# RGMII_Ethernet.net
KiCad netlist of a schematic drawn in Altium Designer
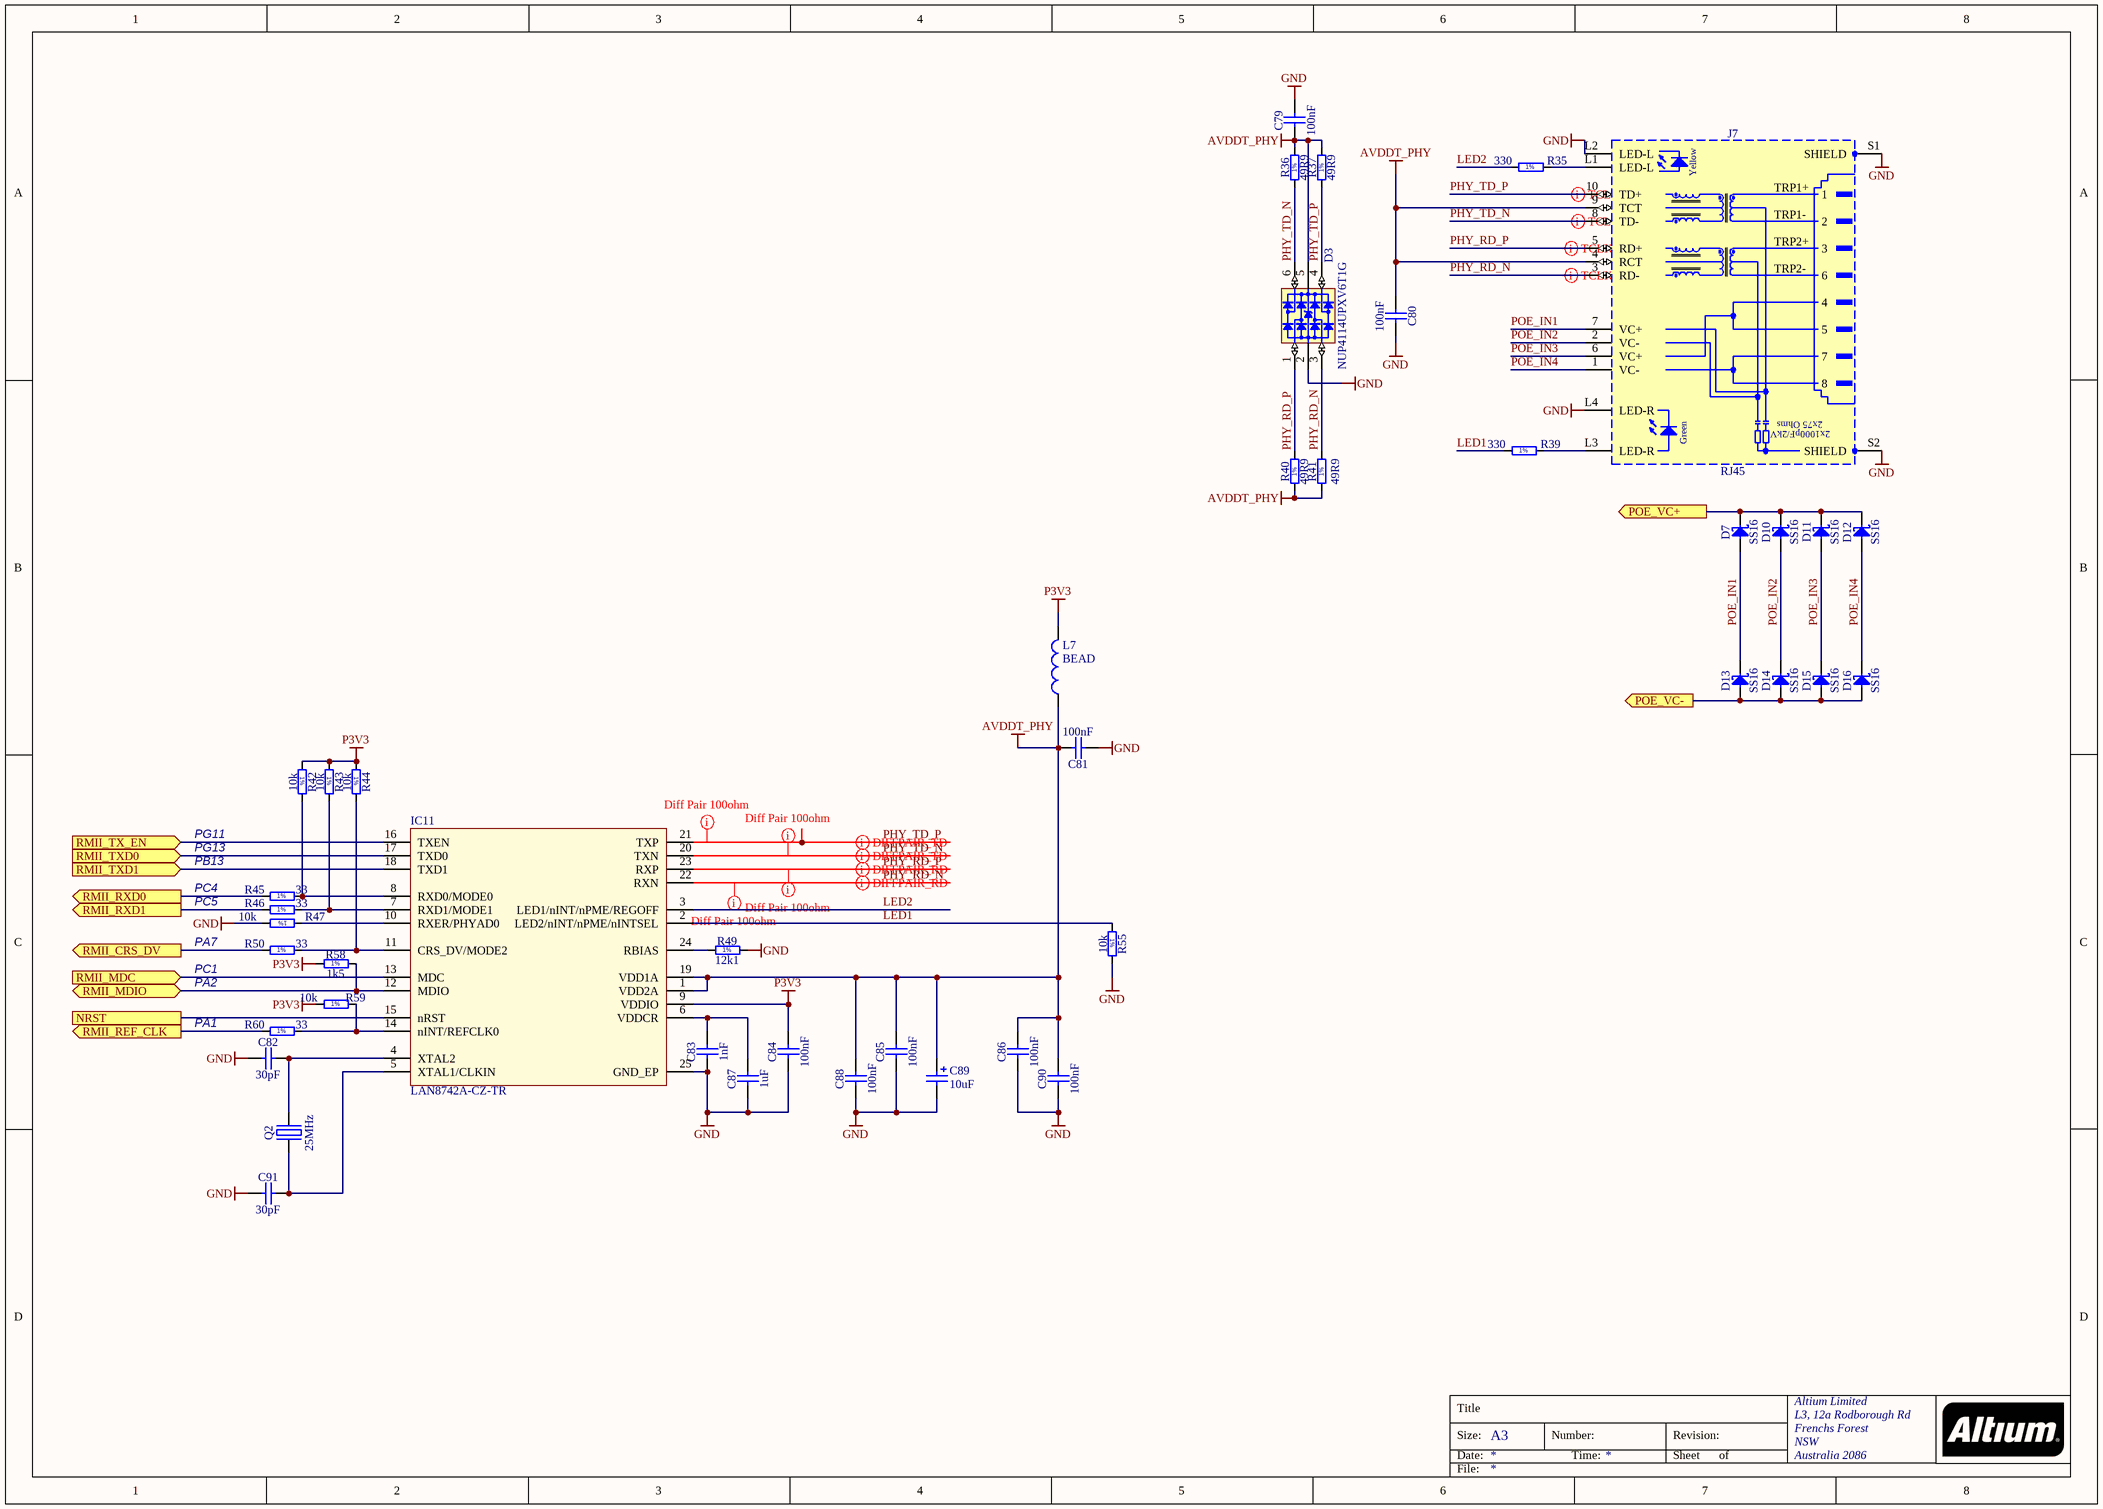
[diagram p0: RGMII_Ethernet.SchDoc]

(export (version "E")
  (design (tool "Eeschema 10.0.6"))
  (components
    (comp (ref "C79")
      (value "100nF")
      (footprint "CAPC1005X55N")
      (description "Non-polarised capacitor")
      (fields
        (field (name "PART NUMBER") "CC0402_100NF_16V_10%_X5R")
        (field (name "VOLTAGE") "16V")
        (field (name "AUTHOR") "CERN DEM JLC")
      )
      (libsource (lib "Capacitors") (part "Capacitor - non polarized"))
    )
    (comp (ref "C80")
      (value "100nF")
      (footprint "CAPC1005X55N")
      (description "Non-polarised capacitor")
      (fields
        (field (name "PART NUMBER") "CC0402_100NF_16V_10%_X5R")
        (field (name "VOLTAGE") "16V")
        (field (name "AUTHOR") "CERN DEM JLC")
      )
      (libsource (lib "Capacitors") (part "Capacitor - non polarized"))
    )
    (comp (ref "C81")
      (value "100nF")
      (footprint "CAPC1005X55N")
      (description "Non-polarised capacitor")
      (fields
        (field (name "PART NUMBER") "CC0402_100NF_16V_10%_X5R")
        (field (name "VOLTAGE") "16V")
        (field (name "AUTHOR") "CERN DEM JLC")
      )
      (libsource (lib "Capacitors") (part "Capacitor - non polarized"))
    )
    (comp (ref "C82")
      (value "30pF")
      (footprint "CAPC1005X55N")
      (description "Non-polarised capacitor")
      (fields
        (field (name "PART NUMBER") "CC0402_30PF_50V_1%_C0G_MURATA_GJM1555C1H300FB01")
        (field (name "VOLTAGE") "50V")
        (field (name "AUTHOR") "CERN DEM BC")
      )
      (libsource (lib "Capacitors") (part "Capacitor - non polarized"))
    )
    (comp (ref "C83")
      (value "1nF")
      (footprint "CAPC1005X55N")
      (description "Non-polarised capacitor")
      (fields
        (field (name "PART NUMBER") "CC0402_1NF_50V_10%_X7R")
        (field (name "VOLTAGE") "50V")
        (field (name "AUTHOR") "CERN DEM JLC")
      )
      (libsource (lib "Capacitors") (part "Capacitor - non polarized"))
    )
    (comp (ref "C84")
      (value "100nF")
      (footprint "CAPC1005X55N")
      (description "Non-polarised capacitor")
      (fields
        (field (name "PART NUMBER") "CC0402_100NF_16V_10%_X5R")
        (field (name "VOLTAGE") "16V")
        (field (name "AUTHOR") "CERN DEM JLC")
      )
      (libsource (lib "Capacitors") (part "Capacitor - non polarized"))
    )
    (comp (ref "C85")
      (value "100nF")
      (footprint "CAPC1005X55N")
      (description "Non-polarised capacitor")
      (fields
        (field (name "PART NUMBER") "CC0402_100NF_16V_10%_X5R")
        (field (name "VOLTAGE") "16V")
        (field (name "AUTHOR") "CERN DEM JLC")
      )
      (libsource (lib "Capacitors") (part "Capacitor - non polarized"))
    )
    (comp (ref "C86")
      (value "100nF")
      (footprint "CAPC1005X55N")
      (description "Non-polarised capacitor")
      (fields
        (field (name "PART NUMBER") "CC0402_100NF_16V_10%_X5R")
        (field (name "VOLTAGE") "16V")
        (field (name "AUTHOR") "CERN DEM JLC")
      )
      (libsource (lib "Capacitors") (part "Capacitor - non polarized"))
    )
    (comp (ref "C87")
      (value "1uF")
      (footprint "CAPC1608X87N")
      (description "Non-polarised capacitor")
      (fields
        (field (name "PART NUMBER") "CC0603_1UF_16V_10%_X7R")
        (field (name "VOLTAGE") "16V")
        (field (name "AUTHOR") "CERN DEM JLC")
      )
      (libsource (lib "Capacitors") (part "Capacitor - non polarized"))
    )
    (comp (ref "C88")
      (value "100nF")
      (footprint "CAPC1005X55N")
      (description "Non-polarised capacitor")
      (fields
        (field (name "PART NUMBER") "CC0402_100NF_16V_10%_X5R")
        (field (name "VOLTAGE") "16V")
        (field (name "AUTHOR") "CERN DEM JLC")
      )
      (libsource (lib "Capacitors") (part "Capacitor - non polarized"))
    )
    (comp (ref "C89")
      (value "10uF")
      (footprint "TAN-A")
      (description "Polarized Capacitor,10uF,10V,10%,typeA,VISHAY")
      (libsource (lib "MCD_TOOLS") (part "Cap_10uF_POL_10%_TANA"))
    )
    (comp (ref "C90")
      (value "100nF")
      (footprint "CAPC1005X55N")
      (description "Non-polarised capacitor")
      (fields
        (field (name "PART NUMBER") "CC0402_100NF_16V_10%_X5R")
        (field (name "VOLTAGE") "16V")
        (field (name "AUTHOR") "CERN DEM JLC")
      )
      (libsource (lib "Capacitors") (part "Capacitor - non polarized"))
    )
    (comp (ref "C91")
      (value "30pF")
      (footprint "CAPC1005X55N")
      (description "Non-polarised capacitor")
      (fields
        (field (name "PART NUMBER") "CC0402_30PF_50V_1%_C0G_MURATA_GJM1555C1H300FB01")
        (field (name "VOLTAGE") "50V")
        (field (name "AUTHOR") "CERN DEM BC")
      )
      (libsource (lib "Capacitors") (part "Capacitor - non polarized"))
    )
    (comp (ref "D3")
      (value "NUP4114UPXV6T1G")
      (footprint "SOTFL50P160X60-6N")
      (fields
        (field (name "VOLTAGE") "5.5V")
        (field (name "MANUFACTURER") "ON SEMICONDUCTOR")
        (field (name "AUTHOR") "CERN DEM JLC")
      )
      (libsource (lib "ICs And Semiconductors") (part "NUP4114"))
    )
    (comp (ref "D7")
      (value "SS16")
      (footprint "DIOM5127X229N")
      (description "Schottky Diode")
      (fields
        (field (name "VOLTAGE") "60V")
        (field (name "POWER") "1A")
        (field (name "AUTHOR") "CERN DEM JLC")
      )
      (libsource (lib "ICs And Semiconductors") (part "Diode Schottky"))
    )
    (comp (ref "D10")
      (value "SS16")
      (footprint "DIOM5127X229N")
      (description "Schottky Diode")
      (fields
        (field (name "VOLTAGE") "60V")
        (field (name "POWER") "1A")
        (field (name "AUTHOR") "CERN DEM JLC")
      )
      (libsource (lib "ICs And Semiconductors") (part "Diode Schottky"))
    )
    (comp (ref "D11")
      (value "SS16")
      (footprint "DIOM5127X229N")
      (description "Schottky Diode")
      (fields
        (field (name "VOLTAGE") "60V")
        (field (name "POWER") "1A")
        (field (name "AUTHOR") "CERN DEM JLC")
      )
      (libsource (lib "ICs And Semiconductors") (part "Diode Schottky"))
    )
    (comp (ref "D12")
      (value "SS16")
      (footprint "DIOM5127X229N")
      (description "Schottky Diode")
      (fields
        (field (name "VOLTAGE") "60V")
        (field (name "POWER") "1A")
        (field (name "AUTHOR") "CERN DEM JLC")
      )
      (libsource (lib "ICs And Semiconductors") (part "Diode Schottky"))
    )
    (comp (ref "D13")
      (value "SS16")
      (footprint "DIOM5127X229N")
      (description "Schottky Diode")
      (fields
        (field (name "VOLTAGE") "60V")
        (field (name "POWER") "1A")
        (field (name "AUTHOR") "CERN DEM JLC")
      )
      (libsource (lib "ICs And Semiconductors") (part "Diode Schottky"))
    )
    (comp (ref "D14")
      (value "SS16")
      (footprint "DIOM5127X229N")
      (description "Schottky Diode")
      (fields
        (field (name "VOLTAGE") "60V")
        (field (name "POWER") "1A")
        (field (name "AUTHOR") "CERN DEM JLC")
      )
      (libsource (lib "ICs And Semiconductors") (part "Diode Schottky"))
    )
    (comp (ref "D15")
      (value "SS16")
      (footprint "DIOM5127X229N")
      (description "Schottky Diode")
      (fields
        (field (name "VOLTAGE") "60V")
        (field (name "POWER") "1A")
        (field (name "AUTHOR") "CERN DEM JLC")
      )
      (libsource (lib "ICs And Semiconductors") (part "Diode Schottky"))
    )
    (comp (ref "D16")
      (value "SS16")
      (footprint "DIOM5127X229N")
      (description "Schottky Diode")
      (fields
        (field (name "VOLTAGE") "60V")
        (field (name "POWER") "1A")
        (field (name "AUTHOR") "CERN DEM JLC")
      )
      (libsource (lib "ICs And Semiconductors") (part "Diode Schottky"))
    )
    (comp (ref "IC11")
      (value "LAN8742A-CZ-TR")
      (footprint "QFN24_0R5_4X4")
      (libsource (lib "LIBRARY_SCH") (part "IFC_LAN8742A"))
    )
    (comp (ref "J7")
      (value "RJ45")
      (footprint "ABRACON_ARJM11C7-114-BA-EW2")
      (description "MagJack 10/100BaseT, PoE+, 1X1, OG/Y, -40 to 85*C, Tab Up, RoHS")
      (fields
        (field (name "PART NUMBER") "ARJM11C7-114-BA-EW2")
        (field (name "MANUFACTURER") "Abracon")
        (field (name "AUTHOR") "GK")
      )
      (libsource (lib "LIBRARY_SCH") (part "CON_ETH_POE_ARJM11C7"))
    )
    (comp (ref "L7")
      (value "BEAD")
      (footprint "0603L")
      (description "Inductor")
      (fields (field (name "PUBLISHER") "Altium Limited"))
      (libsource (lib "Miscellaneous Devices") (part "Inductor"))
    )
    (comp (ref "Q2")
      (value "25MHz")
      (footprint "XTAL_ABRACON_ABLS")
      (description "Quartz Crystal")
      (fields
        (field (name "PART NUMBER") "XTAL_25MHZ_ABRACON_ABLS-25.000MHZ-B2F-T")
        (field (name "MANUFACTURER") "ABRACON")
        (field (name "AUTHOR") "CERN DEM JLC")
      )
      (libsource (lib "ICs And Semiconductors") (part "Quartz Crystal"))
    )
    (comp (ref "R35")
      (value "330")
      (footprint "RESC1005X40N")
      (description "Resistor - 1%")
      (fields
        (field (name "PART NUMBER") "R0402_330R_1%_0.0625W_100PPM")
        (field (name "POWER") "0.0625W")
        (field (name "AUTHOR") "CERN DEM JLC")
      )
      (libsource (lib "Resistors") (part "Resistor - 1%"))
    )
    (comp (ref "R36")
      (value "49R9")
      (footprint "RESC1005X40N")
      (description "Resistor - 1%")
      (fields
        (field (name "PART NUMBER") "R0402_49R9_1%_0.0625W_100PPM")
        (field (name "POWER") "0.0625W")
        (field (name "AUTHOR") "CERN DEM JLC")
      )
      (libsource (lib "Resistors") (part "Resistor - 1%"))
    )
    (comp (ref "R37")
      (value "49R9")
      (footprint "RESC1005X40N")
      (description "Resistor - 1%")
      (fields
        (field (name "PART NUMBER") "R0402_49R9_1%_0.0625W_100PPM")
        (field (name "POWER") "0.0625W")
        (field (name "AUTHOR") "CERN DEM JLC")
      )
      (libsource (lib "Resistors") (part "Resistor - 1%"))
    )
    (comp (ref "R39")
      (value "330")
      (footprint "RESC1005X40N")
      (description "Resistor - 1%")
      (fields
        (field (name "PART NUMBER") "R0402_330R_1%_0.0625W_100PPM")
        (field (name "POWER") "0.0625W")
        (field (name "AUTHOR") "CERN DEM JLC")
      )
      (libsource (lib "Resistors") (part "Resistor - 1%"))
    )
    (comp (ref "R40")
      (value "49R9")
      (footprint "RESC1005X40N")
      (description "Resistor - 1%")
      (fields
        (field (name "PART NUMBER") "R0402_49R9_1%_0.0625W_100PPM")
        (field (name "POWER") "0.0625W")
        (field (name "AUTHOR") "CERN DEM JLC")
      )
      (libsource (lib "Resistors") (part "Resistor - 1%"))
    )
    (comp (ref "R41")
      (value "49R9")
      (footprint "RESC1005X40N")
      (description "Resistor - 1%")
      (fields
        (field (name "PART NUMBER") "R0402_49R9_1%_0.0625W_100PPM")
        (field (name "POWER") "0.0625W")
        (field (name "AUTHOR") "CERN DEM JLC")
      )
      (libsource (lib "Resistors") (part "Resistor - 1%"))
    )
    (comp (ref "R42")
      (value "10k")
      (footprint "RESC1005X40N")
      (description "Resistor - 1%")
      (fields
        (field (name "PART NUMBER") "R0402_10K_1%_0.0625W_100PPM")
        (field (name "POWER") "0.0625W")
        (field (name "AUTHOR") "CERN DEM JLC")
      )
      (libsource (lib "Resistors") (part "Resistor - 1%"))
    )
    (comp (ref "R43")
      (value "10k")
      (footprint "RESC1005X40N")
      (description "Resistor - 1%")
      (fields
        (field (name "PART NUMBER") "R0402_10K_1%_0.0625W_100PPM")
        (field (name "POWER") "0.0625W")
        (field (name "AUTHOR") "CERN DEM JLC")
      )
      (libsource (lib "Resistors") (part "Resistor - 1%"))
    )
    (comp (ref "R44")
      (value "10k")
      (footprint "RESC1005X40N")
      (description "Resistor - 1%")
      (fields
        (field (name "PART NUMBER") "R0402_10K_1%_0.0625W_100PPM")
        (field (name "POWER") "0.0625W")
        (field (name "AUTHOR") "CERN DEM JLC")
      )
      (libsource (lib "Resistors") (part "Resistor - 1%"))
    )
    (comp (ref "R45")
      (value "33")
      (footprint "RESC1005X40N")
      (description "Resistor - 1%")
      (fields
        (field (name "PART NUMBER") "R0402_33R_1%_0.0625W_100PPM")
        (field (name "POWER") "0.0625W")
        (field (name "AUTHOR") "CERN DEM JLC")
      )
      (libsource (lib "Resistors") (part "Resistor - 1%"))
    )
    (comp (ref "R46")
      (value "33")
      (footprint "RESC1005X40N")
      (description "Resistor - 1%")
      (fields
        (field (name "PART NUMBER") "R0402_33R_1%_0.0625W_100PPM")
        (field (name "POWER") "0.0625W")
        (field (name "AUTHOR") "CERN DEM JLC")
      )
      (libsource (lib "Resistors") (part "Resistor - 1%"))
    )
    (comp (ref "R47")
      (value "10k")
      (footprint "RESC1005X40N")
      (description "Resistor - 1%")
      (fields
        (field (name "PART NUMBER") "R0402_10K_1%_0.0625W_100PPM")
        (field (name "POWER") "0.0625W")
        (field (name "AUTHOR") "CERN DEM JLC")
      )
      (libsource (lib "Resistors") (part "Resistor - 1%"))
    )
    (comp (ref "R49")
      (value "12k1")
      (footprint "RESC1005X40N")
      (description "Resistor - 1%")
      (fields
        (field (name "PART NUMBER") "R0402_12K1_1%_0.0625W_100PPM")
        (field (name "POWER") "0.0625W")
        (field (name "AUTHOR") "CERN DEM JLC")
      )
      (libsource (lib "Resistors") (part "Resistor - 1%"))
    )
    (comp (ref "R50")
      (value "33")
      (footprint "RESC1005X40N")
      (description "Resistor - 1%")
      (fields
        (field (name "PART NUMBER") "R0402_33R_1%_0.0625W_100PPM")
        (field (name "POWER") "0.0625W")
        (field (name "AUTHOR") "CERN DEM JLC")
      )
      (libsource (lib "Resistors") (part "Resistor - 1%"))
    )
    (comp (ref "R55")
      (value "10k")
      (footprint "RESC1005X40N")
      (description "Resistor - 1%")
      (fields
        (field (name "PART NUMBER") "R0402_10K_1%_0.0625W_100PPM")
        (field (name "POWER") "0.0625W")
        (field (name "AUTHOR") "CERN DEM JLC")
      )
      (libsource (lib "Resistors") (part "Resistor - 1%"))
    )
    (comp (ref "R58")
      (value "1k5")
      (footprint "RESC1005X40N")
      (description "Resistor - 1%")
      (fields
        (field (name "PART NUMBER") "R0402_1K5_1%_0.0625W_100PPM")
        (field (name "POWER") "0.0625W")
        (field (name "AUTHOR") "CERN DEM JLC")
      )
      (libsource (lib "Resistors") (part "Resistor - 1%"))
    )
    (comp (ref "R59")
      (value "10k")
      (footprint "RESC1005X40N")
      (description "Resistor - 1%")
      (fields
        (field (name "PART NUMBER") "R0402_10K_1%_0.0625W_100PPM")
        (field (name "POWER") "0.0625W")
        (field (name "AUTHOR") "CERN DEM JLC")
      )
      (libsource (lib "Resistors") (part "Resistor - 1%"))
    )
    (comp (ref "R60")
      (value "33")
      (footprint "RESC1005X40N")
      (description "Resistor - 1%")
      (fields
        (field (name "PART NUMBER") "R0402_33R_1%_0.0625W_100PPM")
        (field (name "POWER") "0.0625W")
        (field (name "AUTHOR") "CERN DEM JLC")
      )
      (libsource (lib "Resistors") (part "Resistor - 1%"))
    )
  )
  (nets
    (net (code "1") (name "/LED1") (class "Default")
      (node (ref "IC11") (pin "2") (pinfunction "LED2/nINT/nPME/nINTSEL_2") (pintype "passive"))
      (node (ref "R39") (pin "1") (pinfunction "1_1") (pintype "passive"))
      (node (ref "R55") (pin "1") (pinfunction "1_1") (pintype "passive"))
    )
    (net (code "2") (name "/LED2") (class "Default")
      (node (ref "IC11") (pin "3") (pinfunction "LED1/nINT/nPME/REGOFF_3") (pintype "passive"))
      (node (ref "R35") (pin "1") (pinfunction "1_1") (pintype "passive"))
    )
    (net (code "3") (name "/NRST") (class "Default")
      (node (ref "IC11") (pin "15") (pinfunction "nRST_15") (pintype "passive"))
    )
    (net (code "4") (name "/PHY_RD_N") (class "Default")
      (node (ref "D3") (pin "3") (pinfunction "I/O2_3") (pintype "bidirectional"))
      (node (ref "IC11") (pin "22") (pinfunction "RXN_22") (pintype "passive"))
      (node (ref "J7") (pin "3") (pinfunction "RD-_3") (pintype "bidirectional"))
      (node (ref "R41") (pin "2") (pinfunction "2_2") (pintype "passive"))
    )
    (net (code "5") (name "/PHY_RD_P") (class "Default")
      (node (ref "D3") (pin "1") (pinfunction "I/O1_1") (pintype "bidirectional"))
      (node (ref "IC11") (pin "23") (pinfunction "RXP_23") (pintype "passive"))
      (node (ref "J7") (pin "5") (pinfunction "RD+_5") (pintype "bidirectional"))
      (node (ref "R40") (pin "2") (pinfunction "2_2") (pintype "passive"))
    )
    (net (code "6") (name "/PHY_TD_N") (class "Default")
      (node (ref "D3") (pin "6") (pinfunction "I/O4_6") (pintype "bidirectional"))
      (node (ref "IC11") (pin "20") (pinfunction "TXN_20") (pintype "passive"))
      (node (ref "J7") (pin "8") (pinfunction "TD-_8") (pintype "bidirectional"))
      (node (ref "R36") (pin "1") (pinfunction "1_1") (pintype "passive"))
    )
    (net (code "7") (name "/PHY_TD_P") (class "Default")
      (node (ref "D3") (pin "4") (pinfunction "I/O3_4") (pintype "bidirectional"))
      (node (ref "IC11") (pin "21") (pinfunction "TXP_21") (pintype "passive"))
      (node (ref "J7") (pin "10") (pinfunction "TD+_10") (pintype "bidirectional"))
      (node (ref "R37") (pin "1") (pinfunction "1_1") (pintype "passive"))
    )
    (net (code "8") (name "/POE_IN1") (class "Default")
      (node (ref "D13") (pin "1") (pinfunction "C_1") (pintype "passive"))
      (node (ref "D7") (pin "2") (pinfunction "A_2") (pintype "passive"))
      (node (ref "J7") (pin "7") (pinfunction "VC+_7") (pintype "passive"))
    )
    (net (code "9") (name "/POE_IN2") (class "Default")
      (node (ref "D10") (pin "2") (pinfunction "A_2") (pintype "passive"))
      (node (ref "D14") (pin "1") (pinfunction "C_1") (pintype "passive"))
      (node (ref "J7") (pin "2") (pinfunction "VC-_2") (pintype "passive"))
    )
    (net (code "10") (name "/POE_IN3") (class "Default")
      (node (ref "D11") (pin "2") (pinfunction "A_2") (pintype "passive"))
      (node (ref "D15") (pin "1") (pinfunction "C_1") (pintype "passive"))
      (node (ref "J7") (pin "6") (pinfunction "VC+_6") (pintype "passive"))
    )
    (net (code "11") (name "/POE_IN4") (class "Default")
      (node (ref "D12") (pin "2") (pinfunction "A_2") (pintype "passive"))
      (node (ref "D16") (pin "1") (pinfunction "C_1") (pintype "passive"))
      (node (ref "J7") (pin "1") (pinfunction "VC-_1") (pintype "passive"))
    )
    (net (code "12") (name "/POE_VC+") (class "Default")
      (node (ref "D10") (pin "1") (pinfunction "C_1") (pintype "passive"))
      (node (ref "D11") (pin "1") (pinfunction "C_1") (pintype "passive"))
      (node (ref "D12") (pin "1") (pinfunction "C_1") (pintype "passive"))
      (node (ref "D7") (pin "1") (pinfunction "C_1") (pintype "passive"))
    )
    (net (code "13") (name "/POE_VC-") (class "Default")
      (node (ref "D13") (pin "2") (pinfunction "A_2") (pintype "passive"))
      (node (ref "D14") (pin "2") (pinfunction "A_2") (pintype "passive"))
      (node (ref "D15") (pin "2") (pinfunction "A_2") (pintype "passive"))
      (node (ref "D16") (pin "2") (pinfunction "A_2") (pintype "passive"))
    )
    (net (code "14") (name "/RMII_CRS_DV") (class "Default")
      (node (ref "R50") (pin "1") (pinfunction "1_1") (pintype "passive"))
    )
    (net (code "15") (name "/RMII_MDC") (class "Default")
      (node (ref "IC11") (pin "13") (pinfunction "MDC_13") (pintype "passive"))
    )
    (net (code "16") (name "/RMII_MDIO") (class "Default")
      (node (ref "IC11") (pin "12") (pinfunction "MDIO_12") (pintype "passive"))
      (node (ref "R58") (pin "2") (pinfunction "2_2") (pintype "passive"))
    )
    (net (code "17") (name "/RMII_REF_CLK") (class "Default")
      (node (ref "R60") (pin "1") (pinfunction "1_1") (pintype "passive"))
    )
    (net (code "18") (name "/RMII_RXD0") (class "Default")
      (node (ref "R45") (pin "1") (pinfunction "1_1") (pintype "passive"))
    )
    (net (code "19") (name "/RMII_RXD1") (class "Default")
      (node (ref "R46") (pin "1") (pinfunction "1_1") (pintype "passive"))
    )
    (net (code "20") (name "/RMII_TXD0") (class "Default")
      (node (ref "IC11") (pin "17") (pinfunction "TXD0_17") (pintype "passive"))
    )
    (net (code "21") (name "/RMII_TXD1") (class "Default")
      (node (ref "IC11") (pin "18") (pinfunction "TXD1_18") (pintype "passive"))
    )
    (net (code "22") (name "/RMII_TX_EN") (class "Default")
      (node (ref "IC11") (pin "16") (pinfunction "TXEN_16") (pintype "passive"))
    )
    (net (code "23") (name "AVDDT_PHY") (class "Default")
      (node (ref "C79") (pin "1") (pinfunction "1_1") (pintype "passive"))
      (node (ref "C80") (pin "2") (pinfunction "2_2") (pintype "passive"))
      (node (ref "C81") (pin "2") (pinfunction "2_2") (pintype "passive"))
      (node (ref "C85") (pin "2") (pinfunction "2_2") (pintype "passive"))
      (node (ref "C86") (pin "2") (pinfunction "2_2") (pintype "passive"))
      (node (ref "C88") (pin "2") (pinfunction "2_2") (pintype "passive"))
      (node (ref "C89") (pin "1") (pinfunction "1_1") (pintype "passive"))
      (node (ref "C90") (pin "2") (pinfunction "2_2") (pintype "passive"))
      (node (ref "D3") (pin "5") (pinfunction "VBUS_5") (pintype "power_in"))
      (node (ref "IC11") (pin "1") (pinfunction "VDD2A_1") (pintype "passive"))
      (node (ref "IC11") (pin "19") (pinfunction "VDD1A_19") (pintype "passive"))
      (node (ref "J7") (pin "4") (pinfunction "RCT_4") (pintype "bidirectional"))
      (node (ref "J7") (pin "9") (pinfunction "TCT_9") (pintype "bidirectional"))
      (node (ref "L7") (pin "1") (pinfunction "1_1") (pintype "passive"))
      (node (ref "R36") (pin "2") (pinfunction "2_2") (pintype "passive"))
      (node (ref "R37") (pin "2") (pinfunction "2_2") (pintype "passive"))
      (node (ref "R40") (pin "1") (pinfunction "1_1") (pintype "passive"))
      (node (ref "R41") (pin "1") (pinfunction "1_1") (pintype "passive"))
    )
    (net (code "24") (name "GND") (class "Default")
      (node (ref "C79") (pin "2") (pinfunction "2_2") (pintype "passive"))
      (node (ref "C80") (pin "1") (pinfunction "1_1") (pintype "passive"))
      (node (ref "C81") (pin "1") (pinfunction "1_1") (pintype "passive"))
      (node (ref "C82") (pin "1") (pinfunction "1_1") (pintype "passive"))
      (node (ref "C83") (pin "1") (pinfunction "1_1") (pintype "passive"))
      (node (ref "C84") (pin "1") (pinfunction "1_1") (pintype "passive"))
      (node (ref "C85") (pin "1") (pinfunction "1_1") (pintype "passive"))
      (node (ref "C86") (pin "1") (pinfunction "1_1") (pintype "passive"))
      (node (ref "C87") (pin "1") (pinfunction "1_1") (pintype "passive"))
      (node (ref "C88") (pin "1") (pinfunction "1_1") (pintype "passive"))
      (node (ref "C89") (pin "2") (pinfunction "2_2") (pintype "passive"))
      (node (ref "C90") (pin "1") (pinfunction "1_1") (pintype "passive"))
      (node (ref "C91") (pin "1") (pinfunction "1_1") (pintype "passive"))
      (node (ref "D3") (pin "2") (pinfunction "GND_2") (pintype "power_in"))
      (node (ref "IC11") (pin "25") (pinfunction "GND_EP_25") (pintype "passive"))
      (node (ref "J7") (pin "L2") (pinfunction "LED-L_L2") (pintype "passive"))
      (node (ref "J7") (pin "L4") (pinfunction "LED-R_L4") (pintype "passive"))
      (node (ref "J7") (pin "S1") (pinfunction "SHIELD_S1") (pintype "power_in"))
      (node (ref "J7") (pin "S2") (pinfunction "SHIELD_S2") (pintype "power_in"))
      (node (ref "R47") (pin "2") (pinfunction "2_2") (pintype "passive"))
      (node (ref "R49") (pin "2") (pinfunction "2_2") (pintype "passive"))
      (node (ref "R55") (pin "2") (pinfunction "2_2") (pintype "passive"))
    )
    (net (code "25") (name "Net-(IC11-CRS_DV{slash}MODE2)") (class "Default")
      (node (ref "IC11") (pin "11") (pinfunction "CRS_DV/MODE2_11") (pintype "passive"))
      (node (ref "R44") (pin "2") (pinfunction "2_2") (pintype "passive"))
      (node (ref "R50") (pin "2") (pinfunction "2_2") (pintype "passive"))
    )
    (net (code "26") (name "Net-(IC11-RBIAS)") (class "Default")
      (node (ref "IC11") (pin "24") (pinfunction "RBIAS_24") (pintype "passive"))
      (node (ref "R49") (pin "1") (pinfunction "1_1") (pintype "passive"))
    )
    (net (code "27") (name "Net-(IC11-RXD0{slash}MODE0)") (class "Default")
      (node (ref "IC11") (pin "8") (pinfunction "RXD0/MODE0_8") (pintype "passive"))
      (node (ref "R42") (pin "2") (pinfunction "2_2") (pintype "passive"))
      (node (ref "R45") (pin "2") (pinfunction "2_2") (pintype "passive"))
    )
    (net (code "28") (name "Net-(IC11-RXD1{slash}MODE1)") (class "Default")
      (node (ref "IC11") (pin "7") (pinfunction "RXD1/MODE1_7") (pintype "passive"))
      (node (ref "R43") (pin "2") (pinfunction "2_2") (pintype "passive"))
      (node (ref "R46") (pin "2") (pinfunction "2_2") (pintype "passive"))
    )
    (net (code "29") (name "Net-(IC11-RXER{slash}PHYAD0)") (class "Default")
      (node (ref "IC11") (pin "10") (pinfunction "RXER/PHYAD0_10") (pintype "passive"))
      (node (ref "R47") (pin "1") (pinfunction "1_1") (pintype "passive"))
    )
    (net (code "30") (name "Net-(IC11-VDDCR)") (class "Default")
      (node (ref "C83") (pin "2") (pinfunction "2_2") (pintype "passive"))
      (node (ref "C87") (pin "2") (pinfunction "2_2") (pintype "passive"))
      (node (ref "IC11") (pin "6") (pinfunction "VDDCR_6") (pintype "passive"))
    )
    (net (code "31") (name "Net-(IC11-XTAL1{slash}CLKIN)") (class "Default")
      (node (ref "C91") (pin "2") (pinfunction "2_2") (pintype "passive"))
      (node (ref "IC11") (pin "5") (pinfunction "XTAL1/CLKIN_5") (pintype "passive"))
      (node (ref "Q2") (pin "1") (pinfunction "OSC1_1") (pintype "passive"))
    )
    (net (code "32") (name "Net-(IC11-XTAL2)") (class "Default")
      (node (ref "C82") (pin "2") (pinfunction "2_2") (pintype "passive"))
      (node (ref "IC11") (pin "4") (pinfunction "XTAL2_4") (pintype "passive"))
      (node (ref "Q2") (pin "2") (pinfunction "OSC2_2") (pintype "passive"))
    )
    (net (code "33") (name "Net-(IC11-nINT{slash}REFCLK0)") (class "Default")
      (node (ref "IC11") (pin "14") (pinfunction "nINT/REFCLK0_14") (pintype "passive"))
      (node (ref "R59") (pin "2") (pinfunction "2_2") (pintype "passive"))
      (node (ref "R60") (pin "2") (pinfunction "2_2") (pintype "passive"))
    )
    (net (code "34") (name "Net-(J7-LED-L-PadL1)") (class "Default")
      (node (ref "J7") (pin "L1") (pinfunction "LED-L_L1") (pintype "passive"))
      (node (ref "R35") (pin "2") (pinfunction "2_2") (pintype "passive"))
    )
    (net (code "35") (name "Net-(J7-LED-R-PadL3)") (class "Default")
      (node (ref "J7") (pin "L3") (pinfunction "LED-R_L3") (pintype "passive"))
      (node (ref "R39") (pin "2") (pinfunction "2_2") (pintype "passive"))
    )
    (net (code "36") (name "P3V3") (class "Default")
      (node (ref "C84") (pin "2") (pinfunction "2_2") (pintype "passive"))
      (node (ref "IC11") (pin "9") (pinfunction "VDDIO_9") (pintype "passive"))
      (node (ref "L7") (pin "2") (pinfunction "2_2") (pintype "passive"))
      (node (ref "R42") (pin "1") (pinfunction "1_1") (pintype "passive"))
      (node (ref "R43") (pin "1") (pinfunction "1_1") (pintype "passive"))
      (node (ref "R44") (pin "1") (pinfunction "1_1") (pintype "passive"))
      (node (ref "R58") (pin "1") (pinfunction "1_1") (pintype "passive"))
      (node (ref "R59") (pin "1") (pinfunction "1_1") (pintype "passive"))
    )
  )
)
